# Barometer.net
KiCad netlist of a schematic drawn in Altium Designer
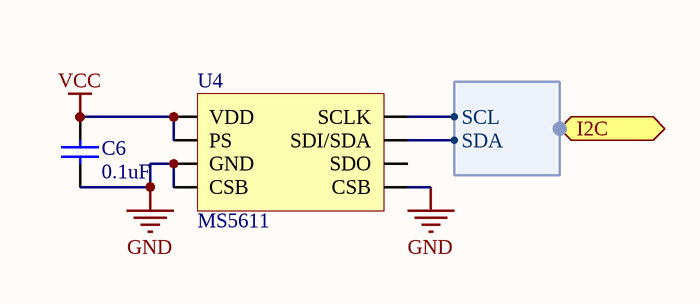
[diagram p0: Barometer.SchDoc]

(export (version "E")
  (design (tool "Eeschema 10.0.6"))
  (components
    (comp (ref "C6")
      (value "0.1uF")
      (footprint "C0402[1005X55]")
      (description "0.1uF 6.3V 10% 0402 (1005 Metric)")
      (fields (field (name "TOLERANCE") "10%") (field (name "PARTNUMBER") "GRM155R70J104KA01D"))
      (libsource (lib "Capacitors") (part "CAP_0.1uF_6.3V_0402_10%"))
    )
    (comp (ref "U4") (value "MS5611") (footprint "MS5611") (libsource (lib "Components") (part "MS5611")))
  )
  (nets
    (net (code "2") (name "/SCL") (class "Default")
      (node (ref "U4") (pin "8") (pinfunction "SCLK_8") (pintype "passive"))
    )
    (net (code "3") (name "/SDA") (class "Default")
      (node (ref "U4") (pin "7") (pinfunction "SDI/SDA_7") (pintype "passive"))
    )
    (net (code "5") (name "GND") (class "Default")
      (node (ref "C6") (pin "1") (pinfunction "1_1") (pintype "passive"))
      (node (ref "U4") (pin "3") (pinfunction "GND_3") (pintype "passive"))
      (node (ref "U4") (pin "4") (pinfunction "CSB_4") (pintype "passive"))
      (node (ref "U4") (pin "5") (pinfunction "CSB_5") (pintype "passive"))
    )
    (net (code "6") (name "VCC") (class "Default")
      (node (ref "C6") (pin "2") (pinfunction "2_2") (pintype "passive"))
      (node (ref "U4") (pin "1") (pinfunction "VDD_1") (pintype "passive"))
      (node (ref "U4") (pin "2") (pinfunction "PS_2") (pintype "passive"))
    )
    (net (code "7") (name "unconnected-(U4-SDO-Pad6)") (class "Default")
      (node (ref "U4") (pin "6") (pinfunction "SDO_6") (pintype "passive"))
    )
  )
)
